# CON_LCD_TX09D50VM1CAA.net
KiCad netlist of a schematic drawn in Altium Designer
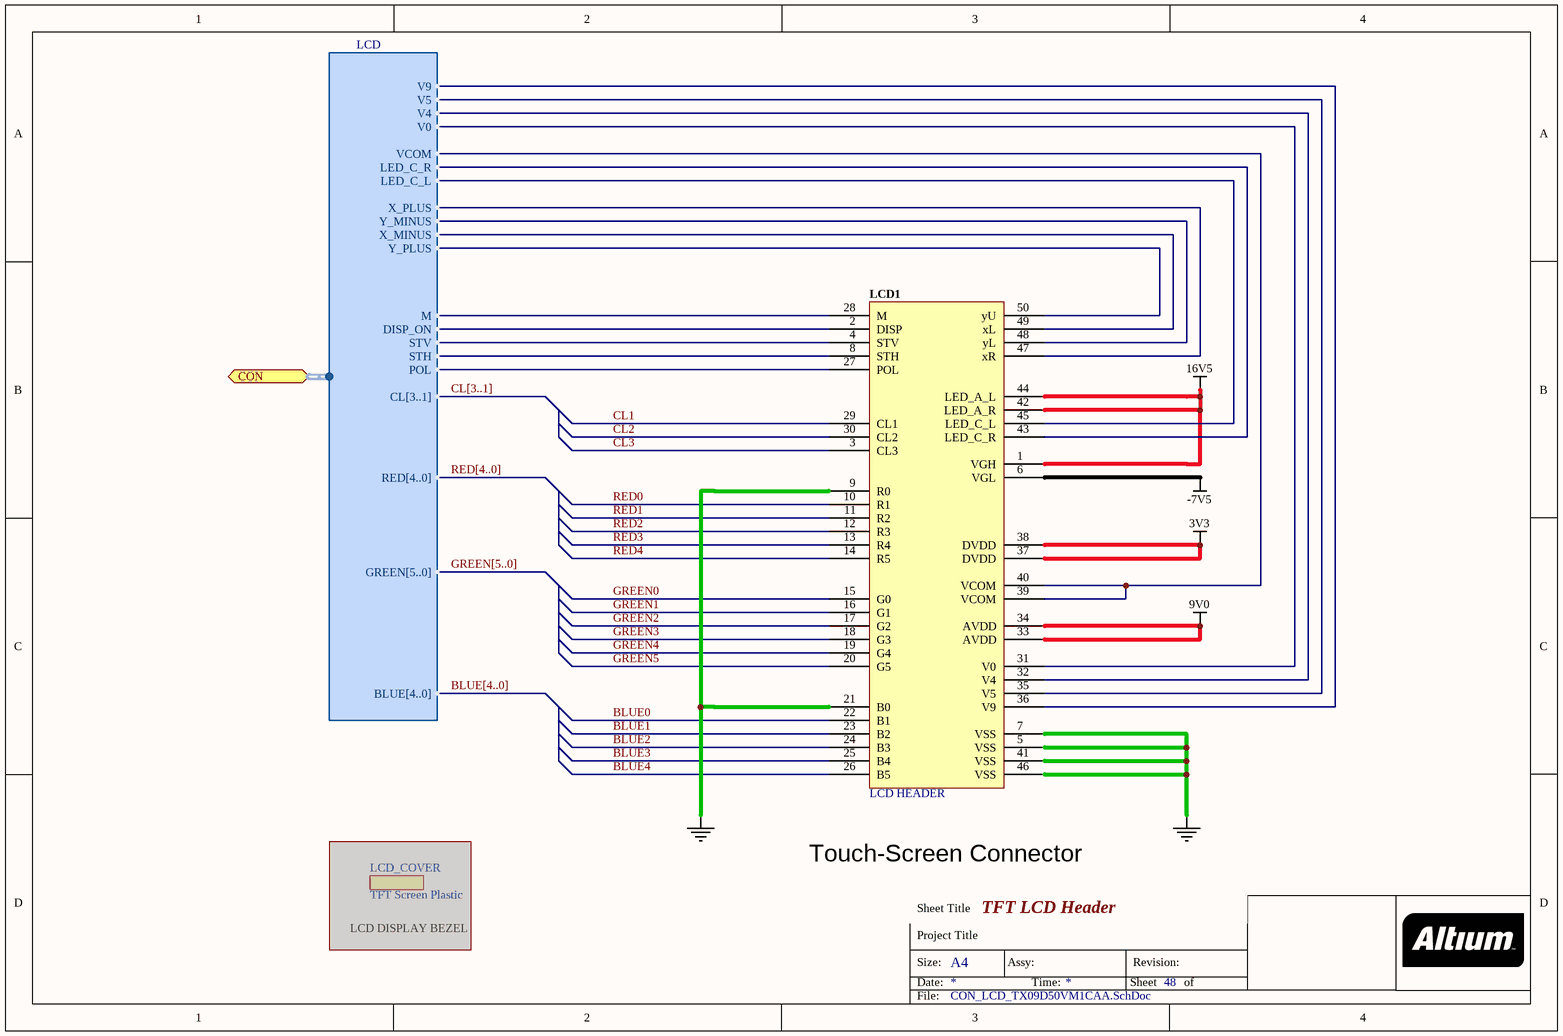
[diagram p0: CON_LCD_TX09D50VM1CAA.SchDoc]

(export (version "E")
  (design (tool "Eeschema 10.0.6"))
  (components
    (comp (ref "LCD1")
      (value "LCD HEADER")
      (footprint "Hitachi_TX09D50VM1CAA")
      (description "Connector, 1 x 50 Pin, 0.5mm Pitch for Hitachi TX09D50VM1CAA TFT")
      (libsource (lib "altium-import") (part "root_0_CON-LCD_"))
    )
    (comp (ref "LCD_COVER")
      (value "TFT Screen Plastic")
      (footprint "NB2 ALTIUM LOGO")
      (libsource (lib "Altium Design Library") (part "Generic No Pins"))
    )
  )
  (nets
    (net (code "2") (name "-7V5") (class "Default")
      (node (ref "LCD1") (pin "6") (pinfunction "VGL_6") (pintype "passive"))
    )
    (net (code "3") (name "/BLUE0") (class "Default")
      (node (ref "LCD1") (pin "22") (pinfunction "B1_22") (pintype "passive"))
    )
    (net (code "4") (name "/BLUE1") (class "Default")
      (node (ref "LCD1") (pin "23") (pinfunction "B2_23") (pintype "passive"))
    )
    (net (code "5") (name "/BLUE2") (class "Default")
      (node (ref "LCD1") (pin "24") (pinfunction "B3_24") (pintype "passive"))
    )
    (net (code "6") (name "/BLUE3") (class "Default")
      (node (ref "LCD1") (pin "25") (pinfunction "B4_25") (pintype "passive"))
    )
    (net (code "7") (name "/BLUE4") (class "Default")
      (node (ref "LCD1") (pin "26") (pinfunction "B5_26") (pintype "passive"))
    )
    (net (code "9") (name "/CL1") (class "Default")
      (node (ref "LCD1") (pin "29") (pinfunction "CL1_29") (pintype "passive"))
    )
    (net (code "10") (name "/CL2") (class "Default")
      (node (ref "LCD1") (pin "30") (pinfunction "CL2_30") (pintype "passive"))
    )
    (net (code "11") (name "/CL3") (class "Default")
      (node (ref "LCD1") (pin "3") (pinfunction "CL3_3") (pintype "passive"))
    )
    (net (code "13") (name "/DISP_ON") (class "Default")
      (node (ref "LCD1") (pin "2") (pinfunction "DISP_2") (pintype "passive"))
    )
    (net (code "14") (name "/GREEN0") (class "Default")
      (node (ref "LCD1") (pin "15") (pinfunction "G0_15") (pintype "passive"))
    )
    (net (code "15") (name "/GREEN1") (class "Default")
      (node (ref "LCD1") (pin "16") (pinfunction "G1_16") (pintype "passive"))
    )
    (net (code "16") (name "/GREEN2") (class "Default")
      (node (ref "LCD1") (pin "17") (pinfunction "G2_17") (pintype "passive"))
    )
    (net (code "17") (name "/GREEN3") (class "Default")
      (node (ref "LCD1") (pin "18") (pinfunction "G3_18") (pintype "passive"))
    )
    (net (code "18") (name "/GREEN4") (class "Default")
      (node (ref "LCD1") (pin "19") (pinfunction "G4_19") (pintype "passive"))
    )
    (net (code "19") (name "/GREEN5") (class "Default")
      (node (ref "LCD1") (pin "20") (pinfunction "G5_20") (pintype "passive"))
    )
    (net (code "21") (name "/LED_C_L") (class "Default")
      (node (ref "LCD1") (pin "45") (pinfunction "LED_C_L_45") (pintype "passive"))
    )
    (net (code "22") (name "/LED_C_R") (class "Default")
      (node (ref "LCD1") (pin "43") (pinfunction "LED_C_R_43") (pintype "passive"))
    )
    (net (code "23") (name "/M") (class "Default")
      (node (ref "LCD1") (pin "28") (pinfunction "M_28") (pintype "passive"))
    )
    (net (code "24") (name "/POL") (class "Default")
      (node (ref "LCD1") (pin "27") (pinfunction "POL_27") (pintype "passive"))
    )
    (net (code "25") (name "/RED0") (class "Default")
      (node (ref "LCD1") (pin "10") (pinfunction "R1_10") (pintype "passive"))
    )
    (net (code "26") (name "/RED1") (class "Default")
      (node (ref "LCD1") (pin "11") (pinfunction "R2_11") (pintype "passive"))
    )
    (net (code "27") (name "/RED2") (class "Default")
      (node (ref "LCD1") (pin "12") (pinfunction "R3_12") (pintype "passive"))
    )
    (net (code "28") (name "/RED3") (class "Default")
      (node (ref "LCD1") (pin "13") (pinfunction "R4_13") (pintype "passive"))
    )
    (net (code "29") (name "/RED4") (class "Default")
      (node (ref "LCD1") (pin "14") (pinfunction "R5_14") (pintype "passive"))
    )
    (net (code "31") (name "/STH") (class "Default")
      (node (ref "LCD1") (pin "8") (pinfunction "STH_8") (pintype "passive"))
    )
    (net (code "32") (name "/STV") (class "Default")
      (node (ref "LCD1") (pin "4") (pinfunction "STV_4") (pintype "passive"))
    )
    (net (code "33") (name "/V0") (class "Default")
      (node (ref "LCD1") (pin "31") (pinfunction "V0_31") (pintype "passive"))
    )
    (net (code "34") (name "/V4") (class "Default")
      (node (ref "LCD1") (pin "32") (pinfunction "V4_32") (pintype "passive"))
    )
    (net (code "35") (name "/V5") (class "Default")
      (node (ref "LCD1") (pin "35") (pinfunction "V5_35") (pintype "passive"))
    )
    (net (code "36") (name "/V9") (class "Default")
      (node (ref "LCD1") (pin "36") (pinfunction "V9_36") (pintype "passive"))
    )
    (net (code "37") (name "/VCOM") (class "Default")
      (node (ref "LCD1") (pin "39") (pinfunction "VCOM_39") (pintype "passive"))
      (node (ref "LCD1") (pin "40") (pinfunction "VCOM_40") (pintype "passive"))
    )
    (net (code "38") (name "/X_MINUS") (class "Default")
      (node (ref "LCD1") (pin "49") (pinfunction "xL_49") (pintype "passive"))
    )
    (net (code "39") (name "/X_PLUS") (class "Default")
      (node (ref "LCD1") (pin "47") (pinfunction "xR_47") (pintype "passive"))
    )
    (net (code "40") (name "/Y_MINUS") (class "Default")
      (node (ref "LCD1") (pin "48") (pinfunction "yL_48") (pintype "passive"))
    )
    (net (code "41") (name "/Y_PLUS") (class "Default")
      (node (ref "LCD1") (pin "50") (pinfunction "yU_50") (pintype "passive"))
    )
    (net (code "43") (name "3V3") (class "Default")
      (node (ref "LCD1") (pin "37") (pinfunction "DVDD_37") (pintype "passive"))
      (node (ref "LCD1") (pin "38") (pinfunction "DVDD_38") (pintype "passive"))
    )
    (net (code "44") (name "9V0") (class "Default")
      (node (ref "LCD1") (pin "33") (pinfunction "AVDD_33") (pintype "passive"))
      (node (ref "LCD1") (pin "34") (pinfunction "AVDD_34") (pintype "passive"))
    )
    (net (code "45") (name "16V5") (class "Default")
      (node (ref "LCD1") (pin "1") (pinfunction "VGH_1") (pintype "passive"))
      (node (ref "LCD1") (pin "42") (pinfunction "LED_A_R_42") (pintype "passive"))
      (node (ref "LCD1") (pin "44") (pinfunction "LED_A_L_44") (pintype "passive"))
    )
    (net (code "46") (name "GND") (class "Default")
      (node (ref "LCD1") (pin "21") (pinfunction "B0_21") (pintype "passive"))
      (node (ref "LCD1") (pin "41") (pinfunction "VSS_41") (pintype "passive"))
      (node (ref "LCD1") (pin "46") (pinfunction "VSS_46") (pintype "passive"))
      (node (ref "LCD1") (pin "5") (pinfunction "VSS_5") (pintype "passive"))
      (node (ref "LCD1") (pin "7") (pinfunction "VSS_7") (pintype "passive"))
      (node (ref "LCD1") (pin "9") (pinfunction "R0_9") (pintype "passive"))
    )
  )
)
